# Divider.net
KiCad netlist of a schematic drawn in Altium Designer
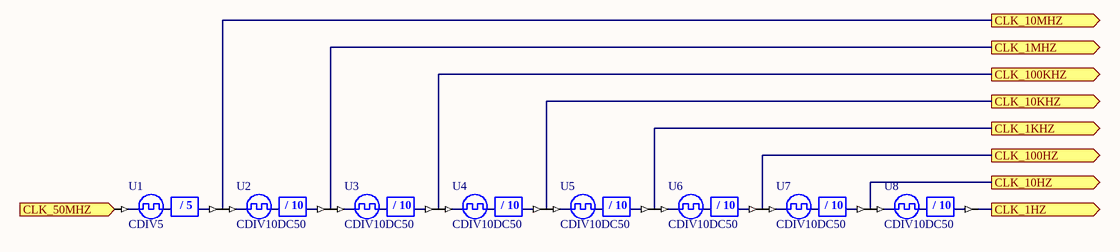
[diagram p0: Divider.SchDoc]

(export (version "E")
  (design (tool "Eeschema 10.0.6"))
  (components
    (comp (ref "U1")
      (value "CDIV5")
      (description "Clock Divider by 5")
      (fields (field (name "PUBLISHER") "Altium Limited"))
      (libsource (lib "FPGA Generic") (part "CDIV5"))
    )
    (comp (ref "U2")
      (value "CDIV10DC50")
      (description "Clock Divider by 10 with 50% Duty Cycle Output")
      (fields (field (name "PUBLISHER") "Altium Limited"))
      (libsource (lib "FPGA Generic") (part "CDIV10DC50"))
    )
    (comp (ref "U3")
      (value "CDIV10DC50")
      (description "Clock Divider by 10 with 50% Duty Cycle Output")
      (fields (field (name "PUBLISHER") "Altium Limited"))
      (libsource (lib "FPGA Generic") (part "CDIV10DC50"))
    )
    (comp (ref "U4")
      (value "CDIV10DC50")
      (description "Clock Divider by 10 with 50% Duty Cycle Output")
      (fields (field (name "PUBLISHER") "Altium Limited"))
      (libsource (lib "FPGA Generic") (part "CDIV10DC50"))
    )
    (comp (ref "U5")
      (value "CDIV10DC50")
      (description "Clock Divider by 10 with 50% Duty Cycle Output")
      (fields (field (name "PUBLISHER") "Altium Limited"))
      (libsource (lib "FPGA Generic") (part "CDIV10DC50"))
    )
    (comp (ref "U6")
      (value "CDIV10DC50")
      (description "Clock Divider by 10 with 50% Duty Cycle Output")
      (fields (field (name "PUBLISHER") "Altium Limited"))
      (libsource (lib "FPGA Generic") (part "CDIV10DC50"))
    )
    (comp (ref "U7")
      (value "CDIV10DC50")
      (description "Clock Divider by 10 with 50% Duty Cycle Output")
      (fields (field (name "PUBLISHER") "Altium Limited"))
      (libsource (lib "FPGA Generic") (part "CDIV10DC50"))
    )
    (comp (ref "U8")
      (value "CDIV10DC50")
      (description "Clock Divider by 10 with 50% Duty Cycle Output")
      (fields (field (name "PUBLISHER") "Altium Limited"))
      (libsource (lib "FPGA Generic") (part "CDIV10DC50"))
    )
  )
  (nets
    (net (code "1") (name "/CLK_1HZ") (class "Default")
      (node (ref "U8") (pin "CLKDV") (pinfunction "CLKDV_CLKDV") (pintype "output"))
    )
    (net (code "2") (name "/CLK_1KHZ") (class "Default")
      (node (ref "U5") (pin "CLKDV") (pinfunction "CLKDV_CLKDV") (pintype "output"))
      (node (ref "U6") (pin "CLKIN") (pinfunction "CLKIN_CLKIN") (pintype "input"))
    )
    (net (code "3") (name "/CLK_1MHZ") (class "Default")
      (node (ref "U2") (pin "CLKDV") (pinfunction "CLKDV_CLKDV") (pintype "output"))
      (node (ref "U3") (pin "CLKIN") (pinfunction "CLKIN_CLKIN") (pintype "input"))
    )
    (net (code "4") (name "/CLK_10HZ") (class "Default")
      (node (ref "U7") (pin "CLKDV") (pinfunction "CLKDV_CLKDV") (pintype "output"))
      (node (ref "U8") (pin "CLKIN") (pinfunction "CLKIN_CLKIN") (pintype "input"))
    )
    (net (code "5") (name "/CLK_10KHZ") (class "Default")
      (node (ref "U4") (pin "CLKDV") (pinfunction "CLKDV_CLKDV") (pintype "output"))
      (node (ref "U5") (pin "CLKIN") (pinfunction "CLKIN_CLKIN") (pintype "input"))
    )
    (net (code "6") (name "/CLK_10MHZ") (class "Default")
      (node (ref "U1") (pin "CLKDV") (pinfunction "CLKDV_CLKDV") (pintype "output"))
      (node (ref "U2") (pin "CLKIN") (pinfunction "CLKIN_CLKIN") (pintype "input"))
    )
    (net (code "7") (name "/CLK_50MHZ") (class "Default")
      (node (ref "U1") (pin "CLKIN") (pinfunction "CLKIN_CLKIN") (pintype "input"))
    )
    (net (code "8") (name "/CLK_100HZ") (class "Default")
      (node (ref "U6") (pin "CLKDV") (pinfunction "CLKDV_CLKDV") (pintype "output"))
      (node (ref "U7") (pin "CLKIN") (pinfunction "CLKIN_CLKIN") (pintype "input"))
    )
    (net (code "9") (name "/CLK_100KHZ") (class "Default")
      (node (ref "U3") (pin "CLKDV") (pinfunction "CLKDV_CLKDV") (pintype "output"))
      (node (ref "U4") (pin "CLKIN") (pinfunction "CLKIN_CLKIN") (pintype "input"))
    )
  )
)
